# Buck.net
KiCad netlist of a schematic drawn in Altium Designer
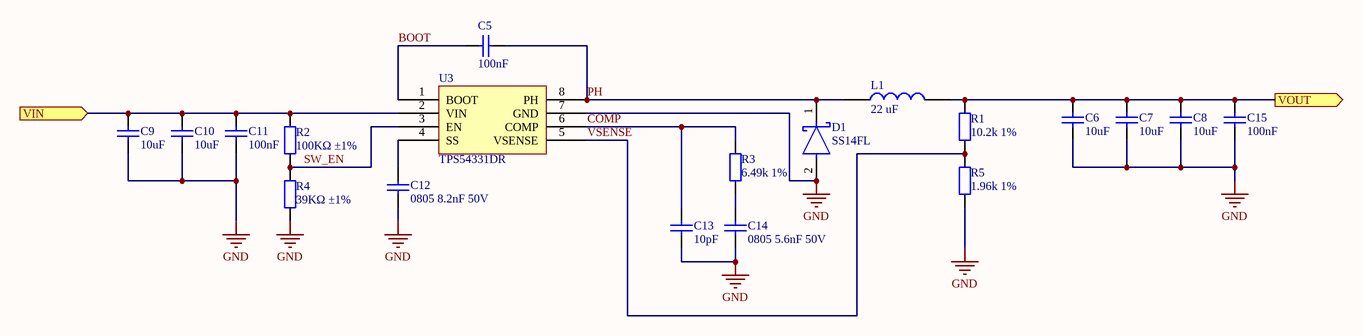
[diagram p0: Buck.SchDoc]

(export (version "E")
  (design (tool "Eeschema 10.0.6"))
  (components
    (comp (ref "C5")
      (value "100nF")
      (footprint "0603_C")
      (description "Chip capacitors")
      (fields (field (name "MANUFACTURER") "YAGEO") (field (name "PARTNUMBER") "CC0603KRX7R9BB104"))
      (libsource (lib "Miscellaneous Devices LC") (part "0603 100nF (104) 10% 50V"))
    )
    (comp (ref "C6")
      (value "10uF")
      (footprint "0603_C")
      (description "Chip capacitors")
      (fields
        (field (name "MANUFACTURER") "Samsung Electro-Mechanics")
        (field (name "PARTNUMBER") "CL10A106KP8NNNC")
      )
      (libsource (lib "Miscellaneous Devices LC") (part "0603 10uF (106) 10% 10V"))
    )
    (comp (ref "C7")
      (value "10uF")
      (footprint "0603_C")
      (description "Chip capacitors")
      (fields
        (field (name "MANUFACTURER") "Samsung Electro-Mechanics")
        (field (name "PARTNUMBER") "CL10A106KP8NNNC")
      )
      (libsource (lib "Miscellaneous Devices LC") (part "0603 10uF (106) 10% 10V"))
    )
    (comp (ref "C8")
      (value "10uF")
      (footprint "0603_C")
      (description "Chip capacitors")
      (fields
        (field (name "MANUFACTURER") "Samsung Electro-Mechanics")
        (field (name "PARTNUMBER") "CL10A106KP8NNNC")
      )
      (libsource (lib "Miscellaneous Devices LC") (part "0603 10uF (106) 10% 10V"))
    )
    (comp (ref "C9")
      (value "10uF")
      (footprint "0805_C")
      (description "Chip capacitors")
      (fields
        (field (name "MANUFACTURER") "Samsung Electro-Mechanics")
        (field (name "PARTNUMBER") "CL21A106KAYNNNE")
      )
      (libsource (lib "Miscellaneous Devices LC") (part "0805 10uF (106) 10% 25V"))
    )
    (comp (ref "C10")
      (value "10uF")
      (footprint "0805_C")
      (description "Chip capacitors")
      (fields
        (field (name "MANUFACTURER") "Samsung Electro-Mechanics")
        (field (name "PARTNUMBER") "CL21A106KAYNNNE")
      )
      (libsource (lib "Miscellaneous Devices LC") (part "0805 10uF (106) 10% 25V"))
    )
    (comp (ref "C11")
      (value "100nF")
      (footprint "0603_C")
      (description "Chip capacitors")
      (fields (field (name "MANUFACTURER") "YAGEO") (field (name "PARTNUMBER") "CC0603KRX7R9BB104"))
      (libsource (lib "Miscellaneous Devices LC") (part "0603 100nF (104) 10% 50V"))
    )
    (comp (ref "C12")
      (value "0805 8.2nF 50V")
      (footprint "Miscellaneous Devices LC:0805_C")
      (fields (field (name "PARTNUMBER") "CL21B822KBANNNC"))
      (libsource (lib "misc") (part "0805 8.2nF 50V"))
    )
    (comp (ref "C13")
      (value "10pF")
      (footprint "0603_C")
      (description "Chip capacitors")
      (fields
        (field (name "MANUFACTURER") "Samsung Electro-Mechanics")
        (field (name "PARTNUMBER") "CL10C100JB8NNNC")
      )
      (libsource (lib "Miscellaneous Devices LC") (part "0603 10pF (100) 5% 50V"))
    )
    (comp (ref "C14")
      (value "0805 5.6nF 50V")
      (footprint "Miscellaneous Devices LC:0805_C")
      (fields (field (name "PARTNUMBER") "CL21B562KBANNNC"))
      (libsource (lib "misc") (part "0805 5.6nF 50V"))
    )
    (comp (ref "C15")
      (value "100nF")
      (footprint "0603_C")
      (description "Chip capacitors")
      (fields (field (name "MANUFACTURER") "YAGEO") (field (name "PARTNUMBER") "CC0603KRX7R9BB104"))
      (libsource (lib "Miscellaneous Devices LC") (part "0603 100nF (104) 10% 50V"))
    )
    (comp (ref "D1")
      (value "SS14FL")
      (footprint "FP-425AD-MFG")
      (description "DIODE SCHOTTKY 40V 1A SOD123F")
      (fields
        (field (name "MANUFACTURER") "ON Semiconductor")
        (field (name "OCTOPART") "https://octopart.com/ss14fl-on+semiconductor-84331601")
      )
      (libsource (lib "Altium Content Vault") (part "c1678fac7984e62e0809fbf79c06691"))
    )
    (comp (ref "L1")
      (value "22 uF")
      (footprint "DR74:COBU-DR74-4R7-R_V")
      (libsource (lib "SWRB1204S-220MT") (part "SRP6540-5R6M"))
    )
    (comp (ref "R1")
      (value "10.2k 1%")
      (footprint "Miscellaneous Devices LC:1206_R")
      (fields (field (name "PARTNUMBER") "1206W4F1022T5E"))
      (libsource (lib "misc") (part "1206 10.2k 1%"))
    )
    (comp (ref "R2")
      (value "100KΩ ±1%")
      (footprint "0805_R")
      (description "Chip resistor")
      (fields (field (name "MANUFACTURER") "Uniroyal Elec") (field (name "POWER") "1/8W"))
      (libsource (lib "Miscellaneous Devices LC") (part "0805 100K (1003) 1%"))
    )
    (comp (ref "R3")
      (value "6.49k 1%")
      (footprint "Miscellaneous Devices LC:0805_R")
      (fields (field (name "PARTNUMBER") "0805W8F6491T5E"))
      (libsource (lib "misc") (part "0805 6.49k 1%"))
    )
    (comp (ref "R4")
      (value "39KΩ ±1%")
      (footprint "0805_R")
      (description "Chip resistor")
      (fields (field (name "MANUFACTURER") "Uniroyal Elec") (field (name "POWER") "1/8W"))
      (libsource (lib "Miscellaneous Devices LC") (part "0805 39K (3902) 1%"))
    )
    (comp (ref "R5")
      (value "1.96k 1%")
      (footprint "Miscellaneous Devices LC:1206_R")
      (fields (field (name "PARTNUMBER") "1206W4F1022T5E"))
      (libsource (lib "misc") (part "1206 1.96k 1%"))
    )
    (comp (ref "U3")
      (value "TPS54331DR")
      (footprint "SOIC-8_150mil")
      (description "DC-DC芯片")
      (libsource (lib "Miscellaneous Devices LC") (part "TPS54331DR_[C9865]"))
    )
  )
  (nets
    (net (code "1") (name "/BOOT") (class "Default")
      (node (ref "C5") (pin "2") (pinfunction "2_2") (pintype "passive"))
      (node (ref "U3") (pin "1") (pinfunction "BOOT_1") (pintype "passive"))
    )
    (net (code "2") (name "/COMP") (class "Default")
      (node (ref "C13") (pin "2") (pinfunction "2_2") (pintype "passive"))
      (node (ref "R3") (pin "2") (pinfunction "2_2") (pintype "passive"))
      (node (ref "U3") (pin "6") (pinfunction "COMP_6") (pintype "passive"))
    )
    (net (code "3") (name "/PH") (class "Default")
      (node (ref "C5") (pin "1") (pinfunction "1_1") (pintype "passive"))
      (node (ref "D1") (pin "1") (pinfunction "C_1") (pintype "passive"))
      (node (ref "L1") (pin "1") (pinfunction "1_1") (pintype "passive"))
      (node (ref "U3") (pin "8") (pinfunction "PH_8") (pintype "passive"))
    )
    (net (code "4") (name "/SW_EN") (class "Default")
      (node (ref "R2") (pin "2") (pinfunction "2_2") (pintype "passive"))
      (node (ref "R4") (pin "2") (pinfunction "2_2") (pintype "passive"))
      (node (ref "U3") (pin "3") (pinfunction "EN_3") (pintype "passive"))
    )
    (net (code "5") (name "/VIN") (class "Default")
      (node (ref "C10") (pin "2") (pinfunction "2_2") (pintype "passive"))
      (node (ref "C11") (pin "2") (pinfunction "2_2") (pintype "passive"))
      (node (ref "C9") (pin "2") (pinfunction "2_2") (pintype "passive"))
      (node (ref "R2") (pin "1") (pinfunction "1_1") (pintype "passive"))
      (node (ref "U3") (pin "2") (pinfunction "VIN_2") (pintype "passive"))
    )
    (net (code "6") (name "/VOUT") (class "Default")
      (node (ref "C15") (pin "2") (pinfunction "2_2") (pintype "passive"))
      (node (ref "C6") (pin "2") (pinfunction "2_2") (pintype "passive"))
      (node (ref "C7") (pin "2") (pinfunction "2_2") (pintype "passive"))
      (node (ref "C8") (pin "2") (pinfunction "2_2") (pintype "passive"))
      (node (ref "L1") (pin "2") (pinfunction "2_2") (pintype "passive"))
      (node (ref "R1") (pin "1") (pinfunction "1_1") (pintype "passive"))
    )
    (net (code "7") (name "/VSENSE") (class "Default")
      (node (ref "R1") (pin "2") (pinfunction "2_2") (pintype "passive"))
      (node (ref "R5") (pin "2") (pinfunction "2_2") (pintype "passive"))
      (node (ref "U3") (pin "5") (pinfunction "VSENSE_5") (pintype "passive"))
    )
    (net (code "8") (name "GND") (class "Default")
      (node (ref "C10") (pin "1") (pinfunction "1_1") (pintype "passive"))
      (node (ref "C11") (pin "1") (pinfunction "1_1") (pintype "passive"))
      (node (ref "C12") (pin "1") (pinfunction "1_1") (pintype "passive"))
      (node (ref "C13") (pin "1") (pinfunction "1_1") (pintype "passive"))
      (node (ref "C14") (pin "1") (pinfunction "1_1") (pintype "passive"))
      (node (ref "C15") (pin "1") (pinfunction "1_1") (pintype "passive"))
      (node (ref "C6") (pin "1") (pinfunction "1_1") (pintype "passive"))
      (node (ref "C7") (pin "1") (pinfunction "1_1") (pintype "passive"))
      (node (ref "C8") (pin "1") (pinfunction "1_1") (pintype "passive"))
      (node (ref "C9") (pin "1") (pinfunction "1_1") (pintype "passive"))
      (node (ref "D1") (pin "2") (pinfunction "A_2") (pintype "passive"))
      (node (ref "R4") (pin "1") (pinfunction "1_1") (pintype "passive"))
      (node (ref "R5") (pin "1") (pinfunction "1_1") (pintype "passive"))
      (node (ref "U3") (pin "7") (pinfunction "GND_7") (pintype "passive"))
    )
    (net (code "9") (name "Net-(C14-Pad2)") (class "Default")
      (node (ref "C14") (pin "2") (pinfunction "2_2") (pintype "passive"))
      (node (ref "R3") (pin "1") (pinfunction "1_1") (pintype "passive"))
    )
    (net (code "10") (name "Net-(U3-SS)") (class "Default")
      (node (ref "C12") (pin "2") (pinfunction "2_2") (pintype "passive"))
      (node (ref "U3") (pin "4") (pinfunction "SS_4") (pintype "passive"))
    )
  )
)
